# schema.net
KiCad netlist of a schematic drawn in EAGLE
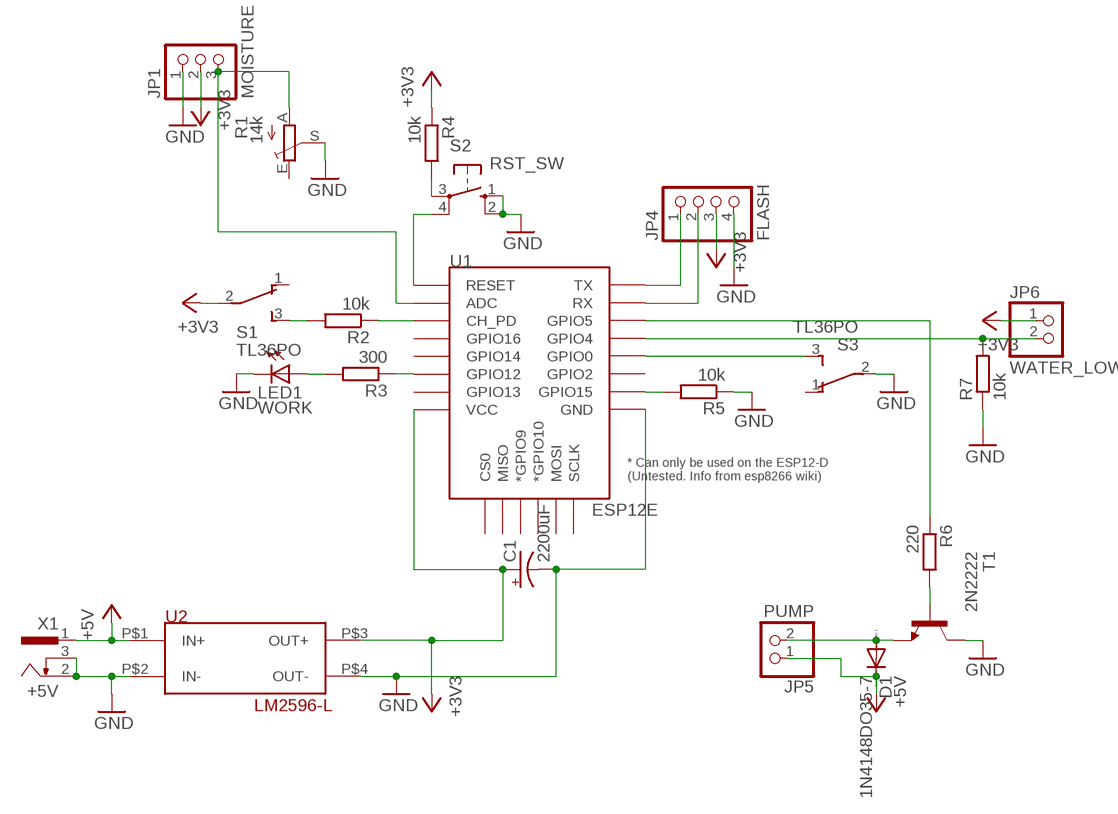
[diagram p0: schematic, sheet 1]

(export (version "E")
  (design (tool "Eeschema 10.0.6"))
  (components
    (comp (ref "C1")
      (value "2200uF")
      (footprint "eagle-import:CPOL-RADIAL-100UF-25V")
      (libsource (lib "eagle-import") (part "100UF-25V-20%(PTH)"))
    )
    (comp (ref "D1")
      (value "1N4148DO35-7")
      (footprint "eagle-import:DO35-7")
      (libsource (lib "eagle-import") (part "1N4148DO35-7"))
    )
    (comp (ref "JP1")
      (value "MOISTURE")
      (footprint "eagle-import:1X03")
      (libsource (lib "eagle-import") (part "PINHD-1X3"))
    )
    (comp (ref "JP4")
      (value "FLASH")
      (footprint "eagle-import:1X04")
      (libsource (lib "eagle-import") (part "PINHD-1X4"))
    )
    (comp (ref "JP5")
      (value "PUMP")
      (footprint "eagle-import:1X02")
      (libsource (lib "eagle-import") (part "PINHD-1X2"))
    )
    (comp (ref "JP6")
      (value "WATER_LOW")
      (footprint "eagle-import:1X02")
      (libsource (lib "eagle-import") (part "PINHD-1X2"))
    )
    (comp (ref "LED1")
      (value "WORK")
      (footprint "eagle-import:LED3MM")
      (libsource (lib "eagle-import") (part "LED3MM"))
    )
    (comp (ref "R1")
      (value "14k")
      (footprint "eagle-import:CA6V")
      (libsource (lib "eagle-import") (part "TRIM_EU-CA6V"))
    )
    (comp (ref "R2")
      (value "10k")
      (footprint "eagle-import:0309V")
      (libsource (lib "eagle-import") (part "R-EU_0309/V"))
    )
    (comp (ref "R3")
      (value "300")
      (footprint "eagle-import:0309V")
      (libsource (lib "eagle-import") (part "R-EU_0309/V"))
    )
    (comp (ref "R4")
      (value "10k")
      (footprint "eagle-import:0309V")
      (libsource (lib "eagle-import") (part "R-EU_0309/V"))
    )
    (comp (ref "R5")
      (value "10k")
      (footprint "eagle-import:0309V")
      (libsource (lib "eagle-import") (part "R-EU_0309/V"))
    )
    (comp (ref "R6")
      (value "220")
      (footprint "eagle-import:0309V")
      (libsource (lib "eagle-import") (part "R-EU_0309/V"))
    )
    (comp (ref "R7")
      (value "10k")
      (footprint "eagle-import:0309V")
      (libsource (lib "eagle-import") (part "R-EU_0309/V"))
    )
    (comp (ref "S1")
      (value "TL36PO")
      (footprint "eagle-import:TL3XPO")
      (libsource (lib "eagle-import") (part "TL36PO"))
    )
    (comp (ref "S2")
      (value "RST_SW")
      (footprint "eagle-import:B3F-10XX")
      (fields (field (name "MPN") "B3F-1000"))
      (libsource (lib "eagle-import") (part "10-XX"))
    )
    (comp (ref "S3")
      (value "TL36PO")
      (footprint "eagle-import:TL3XPO")
      (libsource (lib "eagle-import") (part "TL36PO"))
    )
    (comp (ref "T1")
      (value "2N2222")
      (footprint "eagle-import:TO18")
      (libsource (lib "eagle-import") (part "2N2222"))
    )
    (comp (ref "U1")
      (value "ESP12E")
      (footprint "eagle-import:ESP12E-SMD")
      (libsource (lib "eagle-import") (part "ESP12ESMD"))
    )
    (comp (ref "U2")
      (value "LM2596-L")
      (footprint "eagle-import:LM2596-L")
      (libsource (lib "eagle-import") (part "LM2596-L"))
    )
    (comp (ref "X1")
      (value "+5V")
      (footprint "eagle-import:733989-5")
      (libsource (lib "eagle-import") (part "73398?9-5"))
    )
  )
  (nets
    (net (code "1") (name "+3V3") (class "Default")
      (node (ref "C1") (pin "1") (pinfunction "+_1") (pintype "passive"))
      (node (ref "JP1") (pin "2") (pinfunction "2_2") (pintype "passive"))
      (node (ref "JP4") (pin "3") (pinfunction "3_3") (pintype "passive"))
      (node (ref "JP6") (pin "1") (pinfunction "1_1") (pintype "passive"))
      (node (ref "R4") (pin "1") (pinfunction "1_1") (pintype "passive"))
      (node (ref "S1") (pin "2") (pinfunction "P_2") (pintype "passive"))
      (node (ref "U1") (pin "VCC") (pinfunction "VCC_VCC") (pintype "bidirectional"))
      (node (ref "U2") (pin "P$3") (pinfunction "OUT+_P$3") (pintype "bidirectional"))
    )
    (net (code "2") (name "+5V") (class "Default")
      (node (ref "D1") (pin "C") (pinfunction "C_C") (pintype "passive"))
      (node (ref "JP5") (pin "1") (pinfunction "1_1") (pintype "passive"))
      (node (ref "U2") (pin "P$1") (pinfunction "IN+_P$1") (pintype "bidirectional"))
      (node (ref "X1") (pin "1") (pinfunction "1_1") (pintype "passive"))
    )
    (net (code "3") (name "GND") (class "Default")
      (node (ref "C1") (pin "2") (pinfunction "-_2") (pintype "passive"))
      (node (ref "JP1") (pin "1") (pinfunction "1_1") (pintype "passive"))
      (node (ref "JP4") (pin "4") (pinfunction "4_4") (pintype "passive"))
      (node (ref "LED1") (pin "K") (pinfunction "C_K") (pintype "passive"))
      (node (ref "R1") (pin "S") (pinfunction "S_S") (pintype "passive"))
      (node (ref "R5") (pin "1") (pinfunction "1_1") (pintype "passive"))
      (node (ref "R7") (pin "1") (pinfunction "1_1") (pintype "passive"))
      (node (ref "S2") (pin "1") (pinfunction "S_1") (pintype "passive"))
      (node (ref "S2") (pin "2") (pinfunction "S1_2") (pintype "passive"))
      (node (ref "S3") (pin "2") (pinfunction "P_2") (pintype "passive"))
      (node (ref "T1") (pin "3") (pinfunction "C_3") (pintype "passive"))
      (node (ref "U1") (pin "GND") (pinfunction "GND_GND") (pintype "bidirectional"))
      (node (ref "U2") (pin "P$2") (pinfunction "IN-_P$2") (pintype "bidirectional"))
      (node (ref "U2") (pin "P$4") (pinfunction "OUT-_P$4") (pintype "bidirectional"))
      (node (ref "X1") (pin "2") (pinfunction "2_2") (pintype "passive"))
      (node (ref "X1") (pin "3") (pinfunction "3_3") (pintype "passive"))
    )
    (net (code "4") (name "Net-(JP1-Pad3)") (class "Default")
      (node (ref "JP1") (pin "3") (pinfunction "3_3") (pintype "passive"))
      (node (ref "R1") (pin "A") (pinfunction "A_A") (pintype "passive"))
      (node (ref "U1") (pin "ADC") (pinfunction "ADC_ADC") (pintype "bidirectional"))
    )
    (net (code "5") (name "Net-(JP6-Pad2)") (class "Default")
      (node (ref "JP6") (pin "2") (pinfunction "2_2") (pintype "passive"))
      (node (ref "R7") (pin "2") (pinfunction "2_2") (pintype "passive"))
      (node (ref "U1") (pin "GPIO4") (pinfunction "GPIO4_GPIO4") (pintype "bidirectional"))
    )
    (net (code "6") (name "Net-(LED1-PadA)") (class "Default")
      (node (ref "LED1") (pin "A") (pinfunction "A_A") (pintype "passive"))
      (node (ref "R3") (pin "2") (pinfunction "2_2") (pintype "passive"))
    )
    (net (code "7") (name "Net-(R2-Pad1)") (class "Default")
      (node (ref "R2") (pin "1") (pinfunction "1_1") (pintype "passive"))
      (node (ref "U1") (pin "CH_PD") (pinfunction "CH_PD_CH_PD") (pintype "bidirectional"))
    )
    (net (code "8") (name "Net-(R3-Pad1)") (class "Default")
      (node (ref "R3") (pin "1") (pinfunction "1_1") (pintype "passive"))
      (node (ref "U1") (pin "GPIO12") (pinfunction "GPIO12_GPIO12") (pintype "bidirectional"))
    )
    (net (code "9") (name "Net-(R5-Pad2)") (class "Default")
      (node (ref "R5") (pin "2") (pinfunction "2_2") (pintype "passive"))
      (node (ref "U1") (pin "GPIO15") (pinfunction "GPIO15_GPIO15") (pintype "bidirectional"))
    )
    (net (code "10") (name "Net-(R6-Pad1)") (class "Default")
      (node (ref "R6") (pin "1") (pinfunction "1_1") (pintype "passive"))
      (node (ref "U1") (pin "GPIO5") (pinfunction "GPIO5_GPIO5") (pintype "bidirectional"))
    )
    (net (code "11") (name "Net-(S1-S)") (class "Default")
      (node (ref "R2") (pin "2") (pinfunction "2_2") (pintype "passive"))
      (node (ref "S1") (pin "3") (pinfunction "S_3") (pintype "passive"))
    )
    (net (code "12") (name "Net-(S2-P)") (class "Default")
      (node (ref "R4") (pin "2") (pinfunction "2_2") (pintype "passive"))
      (node (ref "S2") (pin "3") (pinfunction "P_3") (pintype "passive"))
    )
    (net (code "13") (name "Net-(S2-P1)") (class "Default")
      (node (ref "S2") (pin "4") (pinfunction "P1_4") (pintype "passive"))
      (node (ref "U1") (pin "RESET") (pinfunction "RESET_RESET") (pintype "bidirectional"))
    )
    (net (code "14") (name "Net-(S3-S)") (class "Default")
      (node (ref "S3") (pin "3") (pinfunction "S_3") (pintype "passive"))
      (node (ref "U1") (pin "GPIO0") (pinfunction "GPIO0_GPIO0") (pintype "bidirectional"))
    )
    (net (code "15") (name "Net-(T1-B)") (class "Default")
      (node (ref "R6") (pin "2") (pinfunction "2_2") (pintype "passive"))
      (node (ref "T1") (pin "2") (pinfunction "B_2") (pintype "passive"))
    )
    (net (code "16") (name "Net-(T1-E)") (class "Default")
      (node (ref "D1") (pin "A") (pinfunction "A_A") (pintype "passive"))
      (node (ref "JP5") (pin "2") (pinfunction "2_2") (pintype "passive"))
      (node (ref "T1") (pin "1") (pinfunction "E_1") (pintype "passive"))
    )
    (net (code "17") (name "Net-(U1-RX)") (class "Default")
      (node (ref "JP4") (pin "2") (pinfunction "2_2") (pintype "passive"))
      (node (ref "U1") (pin "RXD0") (pinfunction "RX_RXD0") (pintype "bidirectional"))
    )
    (net (code "18") (name "Net-(U1-TX)") (class "Default")
      (node (ref "JP4") (pin "1") (pinfunction "1_1") (pintype "passive"))
      (node (ref "U1") (pin "TXD0") (pinfunction "TX_TXD0") (pintype "bidirectional"))
    )
    (net (code "19") (name "unconnected-(R1-PadE)") (class "Default")
      (node (ref "R1") (pin "E") (pinfunction "E_E") (pintype "passive"))
    )
    (net (code "20") (name "unconnected-(S1-O-Pad1)") (class "Default")
      (node (ref "S1") (pin "1") (pinfunction "O_1") (pintype "passive"))
    )
    (net (code "21") (name "unconnected-(S3-O-Pad1)") (class "Default")
      (node (ref "S3") (pin "1") (pinfunction "O_1") (pintype "passive"))
    )
    (net (code "22") (name "unconnected-(U1-*GPIO9-PadGPIO9)") (class "Default")
      (node (ref "U1") (pin "GPIO9") (pinfunction "*GPIO9_GPIO9") (pintype "bidirectional"))
    )
    (net (code "23") (name "unconnected-(U1-*GPIO10-PadGPIO10)") (class "Default")
      (node (ref "U1") (pin "GPIO10") (pinfunction "*GPIO10_GPIO10") (pintype "bidirectional"))
    )
    (net (code "24") (name "unconnected-(U1-PadCS0)") (class "Default")
      (node (ref "U1") (pin "CS0") (pinfunction "CS0_CS0") (pintype "bidirectional"))
    )
    (net (code "25") (name "unconnected-(U1-PadGPIO2)") (class "Default")
      (node (ref "U1") (pin "GPIO2") (pinfunction "GPIO2_GPIO2") (pintype "bidirectional"))
    )
    (net (code "26") (name "unconnected-(U1-PadGPIO13)") (class "Default")
      (node (ref "U1") (pin "GPIO13") (pinfunction "GPIO13_GPIO13") (pintype "bidirectional"))
    )
    (net (code "27") (name "unconnected-(U1-PadGPIO14)") (class "Default")
      (node (ref "U1") (pin "GPIO14") (pinfunction "GPIO14_GPIO14") (pintype "bidirectional"))
    )
    (net (code "28") (name "unconnected-(U1-PadGPIO16)") (class "Default")
      (node (ref "U1") (pin "GPIO16") (pinfunction "GPIO16_GPIO16") (pintype "bidirectional"))
    )
    (net (code "29") (name "unconnected-(U1-PadMISO)") (class "Default")
      (node (ref "U1") (pin "MISO") (pinfunction "MISO_MISO") (pintype "bidirectional"))
    )
    (net (code "30") (name "unconnected-(U1-PadMOSI)") (class "Default")
      (node (ref "U1") (pin "MOSI") (pinfunction "MOSI_MOSI") (pintype "bidirectional"))
    )
    (net (code "31") (name "unconnected-(U1-PadSCLK)") (class "Default")
      (node (ref "U1") (pin "SCLK") (pinfunction "SCLK_SCLK") (pintype "bidirectional"))
    )
  )
)
